# MIDImike_r3.net
KiCad netlist of a schematic drawn in EAGLE
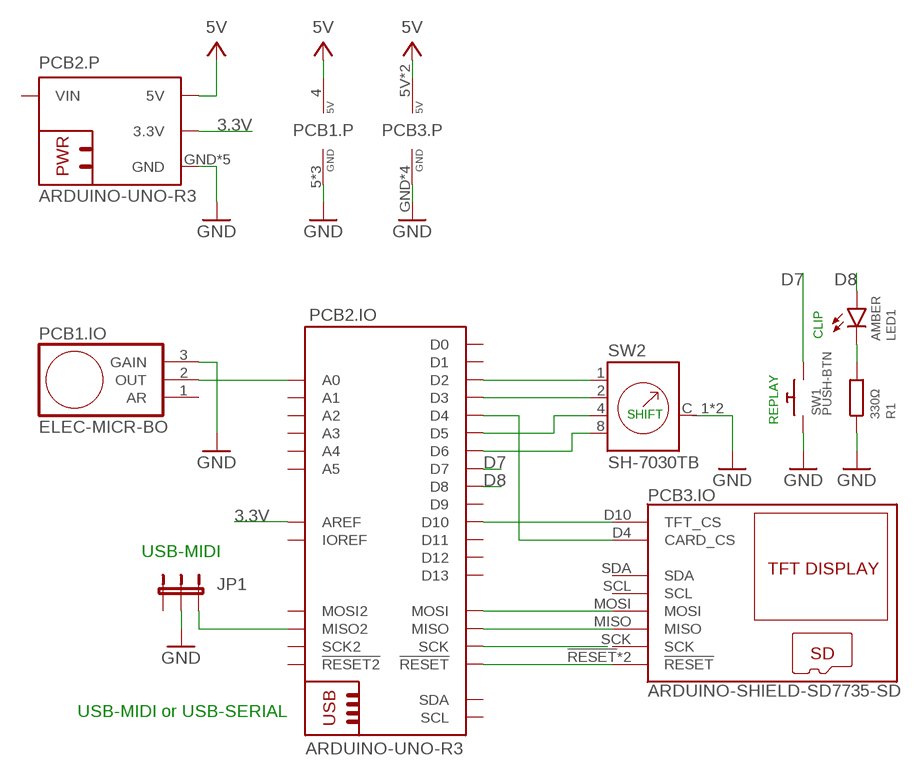
[diagram p0: schematic, sheet 1]

(export (version "E")
  (design (tool "Eeschema 10.0.6"))
  (components
    (comp (ref "JP1")
      (value "JP2E")
      (footprint "eagle-import:JP2")
      (libsource (lib "eagle-import") (part "JP2E"))
    )
    (comp (ref "LED1")
      (value "AMBER")
      (footprint "eagle-import:CHIPLED_0805")
      (libsource (lib "eagle-import") (part "LEDCHIPLED_0805"))
    )
    (comp (ref "PCB1")
      (value "ELEC-MICR-BO")
      (footprint "eagle-import:ELEC_MICR_BREAKOUT")
      (libsource (lib "eagle-import") (part "ELEC-MICR-BO"))
    )
    (comp (ref "PCB2")
      (value "ARDUINO-UNO-R3")
      (footprint "eagle-import:ARDUINO-UNO--R3")
      (libsource (lib "eagle-import") (part "ARDUINO-UNO-R3"))
    )
    (comp (ref "PCB3")
      (value "ARDUINO-SHIELD-SD7735-SD")
      (footprint "eagle-import:ARDIONO-SHIELD")
      (libsource (lib "eagle-import") (part "ARDUINO-SHIELD-SD7735-SD"))
    )
    (comp (ref "R1")
      (value "330Ω")
      (footprint "eagle-import:R0805")
      (fields (field (name "MANF") "Bourns"))
      (libsource (lib "eagle-import") (part "R-EU_R0805"))
    )
    (comp (ref "SW1")
      (value "PUSH-BTN")
      (footprint "eagle-import:TE_1-1825910-4")
      (fields
        (field (name "COMMENT") "1-1825910-4")
        (field (name "DIGI-KEY_PART_NUMBER") "450-1653-ND")
        (field (name "MF") "TE Connectivity")
      )
      (libsource (lib "eagle-import") (part "PUSH-BTN"))
    )
    (comp (ref "SW2")
      (value "SH-7030TB")
      (footprint "eagle-import:SW_RDS-16S-1045-SMT-TR")
      (fields (field (name "MF") "CUI Devices") (field (name "MP") "RDS-16S-1045-SMT-TR"))
      (libsource (lib "eagle-import") (part "SH-7030TB"))
    )
  )
  (nets
    (net (code "1") (name "/3.3V") (class "Default")
      (node (ref "PCB2") (pin "3.3V") (pinfunction "3.3V_3.3V") (pintype "power_in"))
      (node (ref "PCB2") (pin "AREF") (pinfunction "AREF_AREF") (pintype "bidirectional"))
    )
    (net (code "2") (name "/D7") (class "Default")
      (node (ref "PCB2") (pin "D7") (pinfunction "D7_D7") (pintype "bidirectional"))
      (node (ref "SW1") (pin "2") (pinfunction "2_2") (pintype "passive"))
      (node (ref "SW1") (pin "2@1") (pinfunction "2_2@1") (pintype "passive"))
    )
    (net (code "3") (name "/D8") (class "Default")
      (node (ref "LED1") (pin "A") (pinfunction "A_A") (pintype "passive"))
      (node (ref "PCB2") (pin "D8") (pinfunction "D8_D8") (pintype "bidirectional"))
    )
    (net (code "4") (name "/VIN") (class "Default")
      (node (ref "PCB2") (pin "VIN") (pinfunction "VIN_VIN") (pintype "power_in"))
    )
    (net (code "5") (name "5V") (class "Default")
      (node (ref "PCB1") (pin "4") (pinfunction "5V_4") (pintype "passive"))
      (node (ref "PCB2") (pin "5V") (pinfunction "5V_5V") (pintype "power_in"))
      (node (ref "PCB2") (pin "5V@1") (pinfunction "5V_5V@1") (pintype "power_in"))
      (node (ref "PCB2") (pin "5V@2") (pinfunction "5V_5V@2") (pintype "power_in"))
      (node (ref "PCB3") (pin "5V") (pinfunction "5V_5V") (pintype "passive"))
      (node (ref "PCB3") (pin "5V@1") (pinfunction "5V_5V@1") (pintype "passive"))
    )
    (net (code "6") (name "GND") (class "Default")
      (node (ref "JP1") (pin "2") (pinfunction "2_2") (pintype "passive"))
      (node (ref "PCB1") (pin "3") (pinfunction "GAIN_3") (pintype "input"))
      (node (ref "PCB1") (pin "5") (pinfunction "GND_5") (pintype "power_in"))
      (node (ref "PCB1") (pin "P$1") (pinfunction "GND_P$1") (pintype "power_in"))
      (node (ref "PCB1") (pin "P$2") (pinfunction "GND_P$2") (pintype "power_in"))
      (node (ref "PCB2") (pin "GND") (pinfunction "GND_GND") (pintype "power_in"))
      (node (ref "PCB2") (pin "GND@1") (pinfunction "GND_GND@1") (pintype "power_in"))
      (node (ref "PCB2") (pin "GND@2") (pinfunction "GND_GND@2") (pintype "power_in"))
      (node (ref "PCB2") (pin "GND@3") (pinfunction "GND_GND@3") (pintype "power_in"))
      (node (ref "PCB2") (pin "GND@4") (pinfunction "GND_GND@4") (pintype "power_in"))
      (node (ref "PCB3") (pin "GND") (pinfunction "GND_GND") (pintype "power_in"))
      (node (ref "PCB3") (pin "GND@1") (pinfunction "GND_GND@1") (pintype "power_in"))
      (node (ref "PCB3") (pin "GND@2") (pinfunction "GND_GND@2") (pintype "power_in"))
      (node (ref "PCB3") (pin "GND@3") (pinfunction "GND_GND@3") (pintype "power_in"))
      (node (ref "R1") (pin "1") (pinfunction "1_1") (pintype "passive"))
      (node (ref "SW1") (pin "1") (pinfunction "1_1") (pintype "passive"))
      (node (ref "SW1") (pin "1@1") (pinfunction "1_1@1") (pintype "passive"))
      (node (ref "SW2") (pin "C_1") (pinfunction "C_C_1") (pintype "passive"))
      (node (ref "SW2") (pin "C_2") (pinfunction "C_C_2") (pintype "passive"))
    )
    (net (code "7") (name "Net-(JP1-Pad3)") (class "Default")
      (node (ref "JP1") (pin "3") (pinfunction "3_3") (pintype "passive"))
      (node (ref "PCB2") (pin "MISO2") (pinfunction "MISO2_MISO2") (pintype "bidirectional"))
    )
    (net (code "8") (name "Net-(LED1-PadC)") (class "Default")
      (node (ref "LED1") (pin "C") (pinfunction "C_C") (pintype "passive"))
      (node (ref "R1") (pin "2") (pinfunction "2_2") (pintype "passive"))
    )
    (net (code "9") (name "Net-(PCB1A-OUT)") (class "Default")
      (node (ref "PCB1") (pin "2") (pinfunction "OUT_2") (pintype "output"))
      (node (ref "PCB2") (pin "A0") (pinfunction "A0_A0") (pintype "bidirectional"))
    )
    (net (code "10") (name "Net-(PCB2-PadD2)") (class "Default")
      (node (ref "PCB2") (pin "D2") (pinfunction "D2_D2") (pintype "bidirectional"))
      (node (ref "SW2") (pin "1") (pinfunction "1_1") (pintype "passive"))
    )
    (net (code "11") (name "Net-(PCB2-PadD3)") (class "Default")
      (node (ref "PCB2") (pin "D3") (pinfunction "D3_D3") (pintype "bidirectional"))
      (node (ref "SW2") (pin "2") (pinfunction "2_2") (pintype "passive"))
    )
    (net (code "12") (name "Net-(PCB2-PadD5)") (class "Default")
      (node (ref "PCB2") (pin "D5") (pinfunction "D5_D5") (pintype "bidirectional"))
      (node (ref "SW2") (pin "4") (pinfunction "4_4") (pintype "passive"))
    )
    (net (code "13") (name "Net-(PCB2-PadD6)") (class "Default")
      (node (ref "PCB2") (pin "D6") (pinfunction "D6_D6") (pintype "bidirectional"))
      (node (ref "SW2") (pin "8") (pinfunction "8_8") (pintype "passive"))
    )
    (net (code "14") (name "Net-(PCB2-PadMISO)") (class "Default")
      (node (ref "PCB2") (pin "MISO") (pinfunction "MISO_MISO") (pintype "bidirectional"))
      (node (ref "PCB3") (pin "MISO") (pinfunction "MISO_MISO") (pintype "output"))
    )
    (net (code "15") (name "Net-(PCB2-PadMOSI)") (class "Default")
      (node (ref "PCB2") (pin "MOSI") (pinfunction "MOSI_MOSI") (pintype "bidirectional"))
      (node (ref "PCB3") (pin "MOSI") (pinfunction "MOSI_MOSI") (pintype "input"))
    )
    (net (code "16") (name "Net-(PCB2A-~{RESET}-Pad!RESET!)") (class "Default")
      (node (ref "PCB2") (pin "!RESET!") (pinfunction "~{RESET}_!RESET!") (pintype "bidirectional"))
      (node (ref "PCB2") (pin "!RESET!@1") (pinfunction "~{RESET}_!RESET!@1") (pintype "bidirectional"))
      (node (ref "PCB3") (pin "!RESET!") (pinfunction "~{RESET}_!RESET!") (pintype "bidirectional"))
      (node (ref "PCB3") (pin "!RESET!@1") (pinfunction "~{RESET}_!RESET!@1") (pintype "bidirectional"))
    )
    (net (code "17") (name "Net-(PCB3A-CARD_CS)") (class "Default")
      (node (ref "PCB2") (pin "D4") (pinfunction "D4_D4") (pintype "bidirectional"))
      (node (ref "PCB3") (pin "D4") (pinfunction "CARD_CS_D4") (pintype "input"))
    )
    (net (code "18") (name "Net-(PCB3A-TFT_CS)") (class "Default")
      (node (ref "PCB2") (pin "D10") (pinfunction "D10_D10") (pintype "bidirectional"))
      (node (ref "PCB3") (pin "D10") (pinfunction "TFT_CS_D10") (pintype "input"))
    )
    (net (code "19") (name "unconnected-(JP1-Pad1)") (class "Default")
      (node (ref "JP1") (pin "1") (pinfunction "1_1") (pintype "passive"))
    )
    (net (code "20") (name "unconnected-(PCB1A-AR-Pad1)") (class "Default")
      (node (ref "PCB1") (pin "1") (pinfunction "AR_1") (pintype "input"))
    )
    (net (code "21") (name "unconnected-(PCB2-PadA1)") (class "Default")
      (node (ref "PCB2") (pin "A1") (pinfunction "A1_A1") (pintype "bidirectional"))
    )
    (net (code "22") (name "unconnected-(PCB2-PadA2)") (class "Default")
      (node (ref "PCB2") (pin "A2") (pinfunction "A2_A2") (pintype "bidirectional"))
    )
    (net (code "23") (name "unconnected-(PCB2-PadA3)") (class "Default")
      (node (ref "PCB2") (pin "A3") (pinfunction "A3_A3") (pintype "bidirectional"))
    )
    (net (code "24") (name "unconnected-(PCB2-PadA4)") (class "Default")
      (node (ref "PCB2") (pin "A4") (pinfunction "A4_A4") (pintype "bidirectional"))
    )
    (net (code "25") (name "unconnected-(PCB2-PadA5)") (class "Default")
      (node (ref "PCB2") (pin "A5") (pinfunction "A5_A5") (pintype "bidirectional"))
    )
    (net (code "26") (name "unconnected-(PCB2-PadD0)") (class "Default")
      (node (ref "PCB2") (pin "D0") (pinfunction "D0_D0") (pintype "bidirectional"))
    )
    (net (code "27") (name "unconnected-(PCB2-PadD1)") (class "Default")
      (node (ref "PCB2") (pin "D1") (pinfunction "D1_D1") (pintype "bidirectional"))
    )
    (net (code "28") (name "unconnected-(PCB2-PadD9)") (class "Default")
      (node (ref "PCB2") (pin "D9") (pinfunction "D9_D9") (pintype "bidirectional"))
    )
    (net (code "29") (name "unconnected-(PCB2-PadD11)") (class "Default")
      (node (ref "PCB2") (pin "D11") (pinfunction "D11_D11") (pintype "bidirectional"))
    )
    (net (code "30") (name "unconnected-(PCB2-PadD12)") (class "Default")
      (node (ref "PCB2") (pin "D12") (pinfunction "D12_D12") (pintype "bidirectional"))
    )
    (net (code "31") (name "unconnected-(PCB2-PadD13)") (class "Default")
      (node (ref "PCB2") (pin "D13") (pinfunction "D13_D13") (pintype "bidirectional"))
    )
    (net (code "32") (name "unconnected-(PCB2-PadIOREF)") (class "Default")
      (node (ref "PCB2") (pin "IOREF") (pinfunction "IOREF_IOREF") (pintype "bidirectional"))
    )
    (net (code "33") (name "unconnected-(PCB2-PadMOSI2)") (class "Default")
      (node (ref "PCB2") (pin "MOSI2") (pinfunction "MOSI2_MOSI2") (pintype "bidirectional"))
    )
    (net (code "34") (name "unconnected-(PCB2-PadSCK)") (class "Default")
      (node (ref "PCB2") (pin "SCK") (pinfunction "SCK_SCK") (pintype "bidirectional"))
    )
    (net (code "35") (name "unconnected-(PCB2-PadSCK2)") (class "Default")
      (node (ref "PCB2") (pin "SCK2") (pinfunction "SCK2_SCK2") (pintype "bidirectional"))
    )
    (net (code "36") (name "unconnected-(PCB2-PadSCL)") (class "Default")
      (node (ref "PCB2") (pin "SCL") (pinfunction "SCL_SCL") (pintype "bidirectional"))
    )
    (net (code "37") (name "unconnected-(PCB2-PadSDA)") (class "Default")
      (node (ref "PCB2") (pin "SDA") (pinfunction "SDA_SDA") (pintype "bidirectional"))
    )
    (net (code "38") (name "unconnected-(PCB2A-~{RESET2}-Pad!RESET2!)") (class "Default")
      (node (ref "PCB2") (pin "!RESET2!") (pinfunction "~{RESET2}_!RESET2!") (pintype "bidirectional"))
    )
    (net (code "39") (name "unconnected-(PCB3-PadSCK)") (class "Default")
      (node (ref "PCB3") (pin "SCK") (pinfunction "SCK_SCK") (pintype "input"))
    )
    (net (code "40") (name "unconnected-(PCB3-PadSCL)") (class "Default")
      (node (ref "PCB3") (pin "SCL") (pinfunction "SCL_SCL") (pintype "input"))
    )
    (net (code "41") (name "unconnected-(PCB3-PadSDA)") (class "Default")
      (node (ref "PCB3") (pin "SDA") (pinfunction "SDA_SDA") (pintype "bidirectional"))
    )
  )
)
